# 04_LemonAutopilot_5.net
KiCad netlist of a schematic drawn in Altium Designer
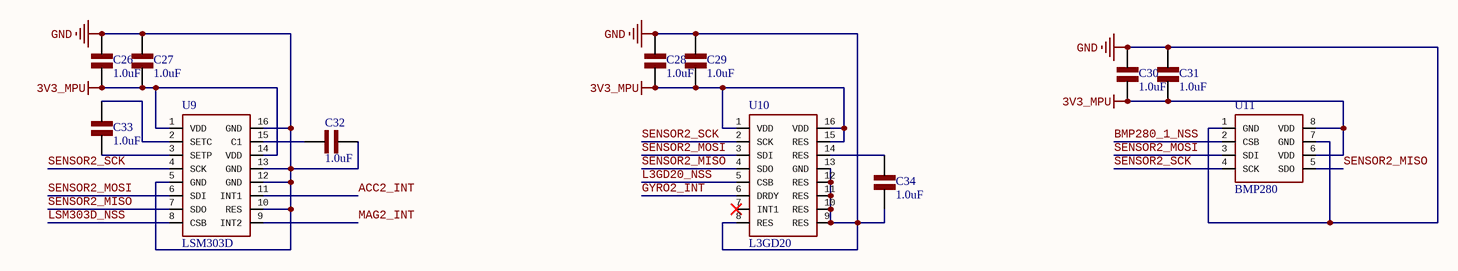
[diagram p0: 04.LemonAutopilot_5.SchDoc]

(export (version "E")
  (design (tool "Eeschema 10.0.6"))
  (components
    (comp (ref "C26") (value "1.0uF") (footprint "0603_C") (libsource (lib "Library") (part "C0603")))
    (comp (ref "C27") (value "1.0uF") (footprint "0603_C") (libsource (lib "Library") (part "C0603")))
    (comp (ref "C28") (value "1.0uF") (footprint "0603_C") (libsource (lib "Library") (part "C0603")))
    (comp (ref "C29") (value "1.0uF") (footprint "0603_C") (libsource (lib "Library") (part "C0603")))
    (comp (ref "C30") (value "1.0uF") (footprint "0603_C") (libsource (lib "") (part "C0603_2")))
    (comp (ref "C31") (value "1.0uF") (footprint "0603_C") (libsource (lib "") (part "C0603_2")))
    (comp (ref "C32") (value "1.0uF") (footprint "0603_C") (libsource (lib "") (part "C0603_1")))
    (comp (ref "C33") (value "1.0uF") (footprint "0603_C") (libsource (lib "Library") (part "C0603")))
    (comp (ref "C34") (value "1.0uF") (footprint "0603_C") (libsource (lib "Library") (part "C0603")))
    (comp (ref "U9") (value "LSM303D") (libsource (lib "Library") (part "LSM303D")))
    (comp (ref "U10") (value "L3GD20") (libsource (lib "Library") (part "L3GD20")))
    (comp (ref "U11") (value "BMP280") (libsource (lib "Library") (part "BMP280")))
  )
  (nets
    (net (code "1") (name "/ACC2_INT") (class "Default")
      (node (ref "U9") (pin "11") (pinfunction "INT1_11") (pintype "passive"))
    )
    (net (code "2") (name "/BMP280_1_NSS") (class "Default")
      (node (ref "U11") (pin "2") (pinfunction "CSB_2") (pintype "passive"))
    )
    (net (code "3") (name "/GYRO2_INT") (class "Default")
      (node (ref "U10") (pin "6") (pinfunction "DRDY_6") (pintype "passive"))
    )
    (net (code "4") (name "/L3GD20_NSS") (class "Default")
      (node (ref "U10") (pin "5") (pinfunction "CSB_5") (pintype "passive"))
    )
    (net (code "5") (name "/LSM303D_NSS") (class "Default")
      (node (ref "U9") (pin "8") (pinfunction "CSB_8") (pintype "passive"))
    )
    (net (code "6") (name "/MAG2_INT") (class "Default")
      (node (ref "U9") (pin "9") (pinfunction "INT2_9") (pintype "passive"))
    )
    (net (code "7") (name "/SENSOR2_MISO") (class "Default")
      (node (ref "U10") (pin "4") (pinfunction "SDO_4") (pintype "passive"))
      (node (ref "U11") (pin "5") (pinfunction "SDO_5") (pintype "passive"))
      (node (ref "U9") (pin "7") (pinfunction "SDO_7") (pintype "passive"))
    )
    (net (code "8") (name "/SENSOR2_MOSI") (class "Default")
      (node (ref "U10") (pin "3") (pinfunction "SDI_3") (pintype "passive"))
      (node (ref "U11") (pin "3") (pinfunction "SDI_3") (pintype "passive"))
      (node (ref "U9") (pin "6") (pinfunction "SDI_6") (pintype "passive"))
    )
    (net (code "9") (name "/SENSOR2_SCK") (class "Default")
      (node (ref "U10") (pin "2") (pinfunction "SCK_2") (pintype "passive"))
      (node (ref "U11") (pin "4") (pinfunction "SCK_4") (pintype "passive"))
      (node (ref "U9") (pin "4") (pinfunction "SCK_4") (pintype "passive"))
    )
    (net (code "10") (name "3V3_MPU") (class "Default")
      (node (ref "C26") (pin "1") (pinfunction "1_1") (pintype "passive"))
      (node (ref "C27") (pin "1") (pinfunction "1_1") (pintype "passive"))
      (node (ref "C28") (pin "1") (pinfunction "1_1") (pintype "passive"))
      (node (ref "C29") (pin "1") (pinfunction "1_1") (pintype "passive"))
      (node (ref "C30") (pin "2") (pinfunction "2_2") (pintype "passive"))
      (node (ref "C31") (pin "2") (pinfunction "2_2") (pintype "passive"))
      (node (ref "U10") (pin "1") (pinfunction "VDD_1") (pintype "passive"))
      (node (ref "U10") (pin "15") (pinfunction "RES_15") (pintype "passive"))
      (node (ref "U10") (pin "16") (pinfunction "VDD_16") (pintype "passive"))
      (node (ref "U11") (pin "6") (pinfunction "VDD_6") (pintype "passive"))
      (node (ref "U11") (pin "8") (pinfunction "VDD_8") (pintype "passive"))
      (node (ref "U9") (pin "1") (pinfunction "VDD_1") (pintype "passive"))
      (node (ref "U9") (pin "14") (pinfunction "VDD_14") (pintype "passive"))
    )
    (net (code "11") (name "GND") (class "Default")
      (node (ref "C26") (pin "2") (pinfunction "2_2") (pintype "passive"))
      (node (ref "C27") (pin "2") (pinfunction "2_2") (pintype "passive"))
      (node (ref "C28") (pin "2") (pinfunction "2_2") (pintype "passive"))
      (node (ref "C29") (pin "2") (pinfunction "2_2") (pintype "passive"))
      (node (ref "C30") (pin "1") (pinfunction "1_1") (pintype "passive"))
      (node (ref "C31") (pin "1") (pinfunction "1_1") (pintype "passive"))
      (node (ref "C32") (pin "1") (pinfunction "1_1") (pintype "passive"))
      (node (ref "C34") (pin "1") (pinfunction "1_1") (pintype "passive"))
      (node (ref "U10") (pin "10") (pinfunction "RES_10") (pintype "passive"))
      (node (ref "U10") (pin "11") (pinfunction "RES_11") (pintype "passive"))
      (node (ref "U10") (pin "12") (pinfunction "RES_12") (pintype "passive"))
      (node (ref "U10") (pin "13") (pinfunction "GND_13") (pintype "passive"))
      (node (ref "U10") (pin "8") (pinfunction "RES_8") (pintype "passive"))
      (node (ref "U10") (pin "9") (pinfunction "RES_9") (pintype "passive"))
      (node (ref "U11") (pin "1") (pinfunction "GND_1") (pintype "passive"))
      (node (ref "U11") (pin "7") (pinfunction "GND_7") (pintype "passive"))
      (node (ref "U9") (pin "10") (pinfunction "RES_10") (pintype "passive"))
      (node (ref "U9") (pin "12") (pinfunction "GND_12") (pintype "passive"))
      (node (ref "U9") (pin "13") (pinfunction "GND_13") (pintype "passive"))
      (node (ref "U9") (pin "16") (pinfunction "GND_16") (pintype "passive"))
      (node (ref "U9") (pin "5") (pinfunction "GND_5") (pintype "passive"))
    )
    (net (code "12") (name "Net-(C34-Pad2)") (class "Default")
      (node (ref "C34") (pin "2") (pinfunction "2_2") (pintype "passive"))
      (node (ref "U10") (pin "14") (pinfunction "RES_14") (pintype "passive"))
    )
    (net (code "13") (name "Net-(U9-C1)") (class "Default")
      (node (ref "C32") (pin "2") (pinfunction "2_2") (pintype "passive"))
      (node (ref "U9") (pin "15") (pinfunction "C1_15") (pintype "passive"))
    )
    (net (code "14") (name "Net-(U9-SETC)") (class "Default")
      (node (ref "C33") (pin "2") (pinfunction "2_2") (pintype "passive"))
      (node (ref "U9") (pin "2") (pinfunction "SETC_2") (pintype "passive"))
    )
    (net (code "15") (name "Net-(U9-SETP)") (class "Default")
      (node (ref "C33") (pin "1") (pinfunction "1_1") (pintype "passive"))
      (node (ref "U9") (pin "3") (pinfunction "SETP_3") (pintype "passive"))
    )
    (net (code "16") (name "unconnected-(U10-INT1-Pad7)") (class "Default")
      (node (ref "U10") (pin "7") (pinfunction "INT1_7") (pintype "passive+no_connect"))
    )
  )
)
